# CADDX_v1.net
KiCad netlist of a schematic drawn in Altium Designer
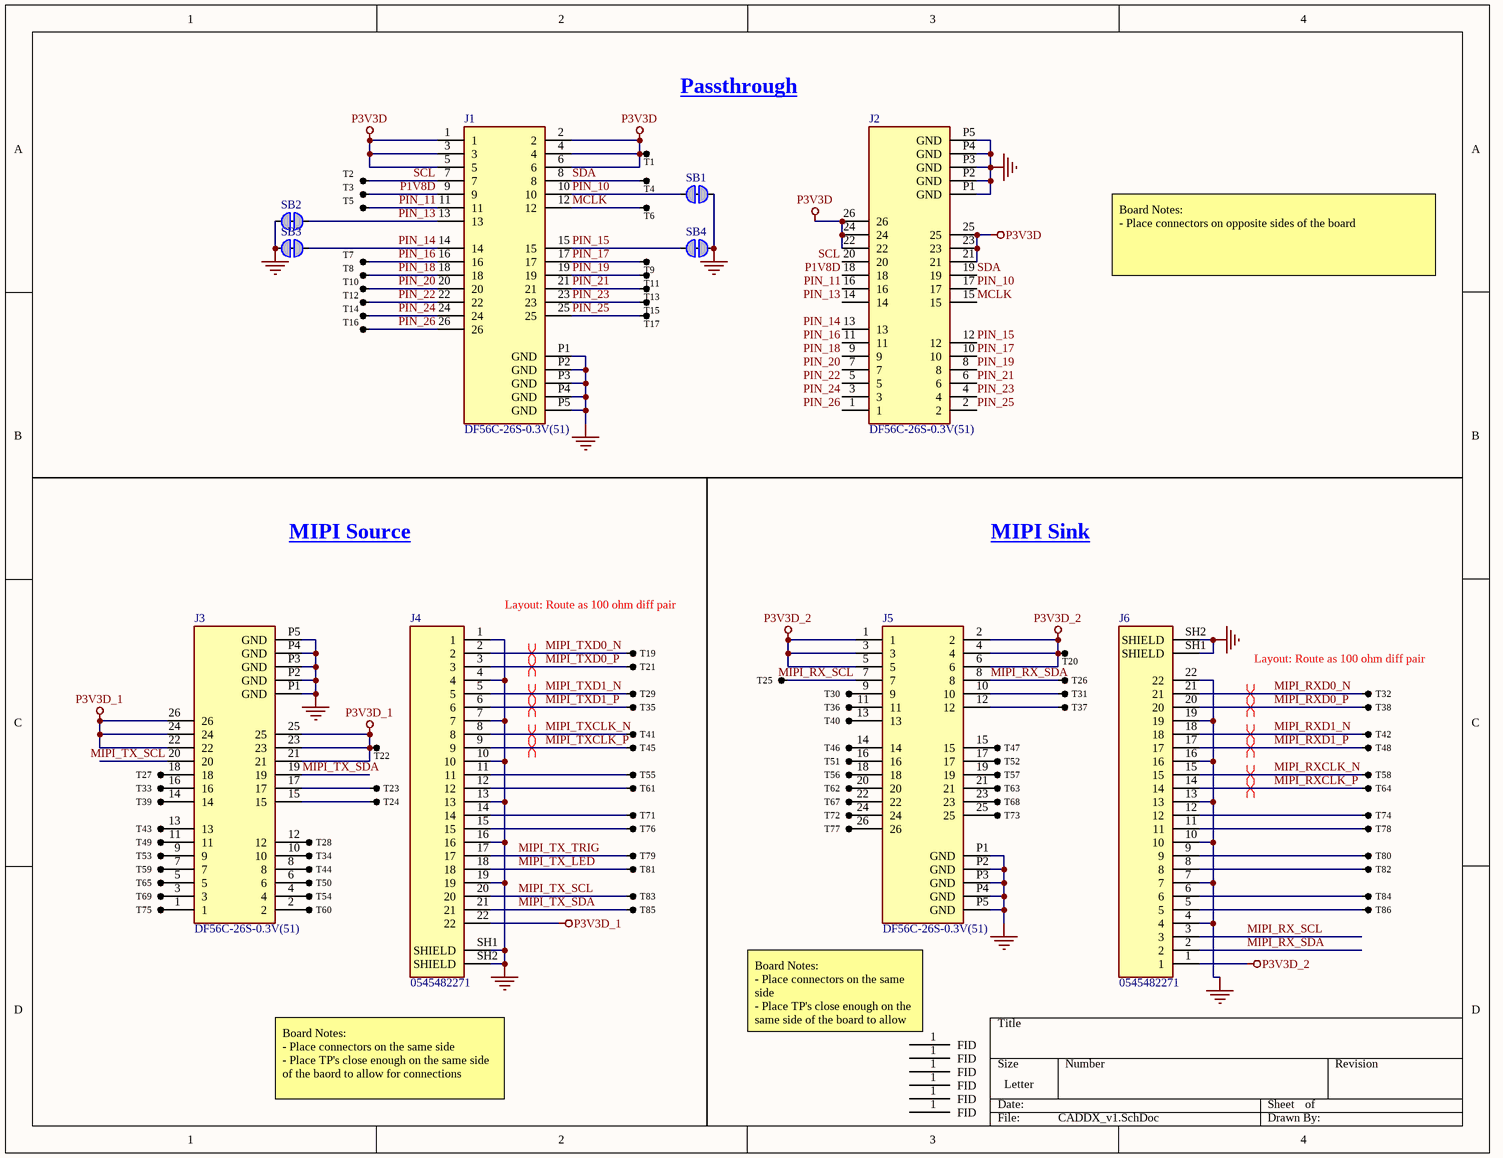
[diagram p0: CADDX_v1.SchDoc]

(export (version "E")
  (design (tool "Eeschema 10.0.6"))
  (components
    (comp (ref "FID1") (value "FID") (footprint "FID_040") (libsource (lib "AiC RVP Adapter") (part "FID")))
    (comp (ref "FID2") (value "FID") (footprint "FID_040") (libsource (lib "AiC RVP Adapter") (part "FID")))
    (comp (ref "FID3") (value "FID") (footprint "FID_040") (libsource (lib "AiC RVP Adapter") (part "FID")))
    (comp (ref "FID4") (value "FID") (footprint "FID_040") (libsource (lib "AiC RVP Adapter") (part "FID")))
    (comp (ref "FID5") (value "FID") (footprint "FID_040") (libsource (lib "AiC RVP Adapter") (part "FID")))
    (comp (ref "FID6") (value "FID") (footprint "FID_040") (libsource (lib "AiC RVP Adapter") (part "FID")))
    (comp (ref "J1")
      (value "DF56C-26S-0.3V(51)")
      (footprint "HRS_DF56C-26S-0.3V(51)")
      (description "0.3mm Pitch, Vertical Mating, Board-to-Fine Coaxial Cable, -35 ℃ to 85 ℃, RoHS")
      (fields (field (name "MANUFACTURER") "Hirose"))
      (libsource (lib "CADDX_passthrough") (part "DF56C-26S-0.3V(51)"))
    )
    (comp (ref "J2")
      (value "DF56C-26S-0.3V(51)")
      (footprint "HRS_DF56C-26S-0.3V(51)")
      (description "0.3mm Pitch, Vertical Mating, Board-to-Fine Coaxial Cable, -35 ℃ to 85 ℃, RoHS")
      (fields (field (name "MANUFACTURER") "Hirose"))
      (libsource (lib "") (part "DF56C-26S-0.3V(51)_1"))
    )
    (comp (ref "J3")
      (value "DF56C-26S-0.3V(51)")
      (footprint "HRS_DF56C-26S-0.3V(51)")
      (description "0.3mm Pitch, Vertical Mating, Board-to-Fine Coaxial Cable, -35 ℃ to 85 ℃, RoHS")
      (fields (field (name "MANUFACTURER") "Hirose"))
      (libsource (lib "") (part "DF56C-26S-0.3V(51)_1"))
    )
    (comp (ref "J4")
      (value "0545482271")
      (footprint "MOLEX_54548-2271")
      (description "CONN FFC BOTTOM 22POS 0.50MM R/A")
      (fields (field (name "MANUFACTURER") "Molex"))
      (libsource (lib "CADDX_passthrough") (part "54548-2271"))
    )
    (comp (ref "J5")
      (value "DF56C-26S-0.3V(51)")
      (footprint "HRS_DF56C-26S-0.3V(51)")
      (description "0.3mm Pitch, Vertical Mating, Board-to-Fine Coaxial Cable, -35 ℃ to 85 ℃, RoHS")
      (fields (field (name "MANUFACTURER") "Hirose"))
      (libsource (lib "CADDX_passthrough") (part "DF56C-26S-0.3V(51)"))
    )
    (comp (ref "J6")
      (value "0545482271")
      (footprint "MOLEX_54548-2271")
      (description "CONN FFC BOTTOM 22POS 0.50MM R/A")
      (fields (field (name "MANUFACTURER") "Molex"))
      (libsource (lib "") (part "54548-2271_1"))
    )
    (comp (ref "SB1")
      (value "Solderbridge")
      (footprint "Solderbridge_Shorted")
      (description "Shorted Solderbridge")
      (fields
        (field (name "PART NUMBER") "Solderbridge Shorted")
        (field (name "PUBLISHER") "Nordic Semiconductor")
      )
      (libsource (lib "Tiger_Ti180") (part "Solderbridge Shorted"))
    )
    (comp (ref "SB2")
      (value "Solderbridge")
      (footprint "Solderbridge_Shorted")
      (description "Shorted Solderbridge")
      (fields
        (field (name "PART NUMBER") "Solderbridge Shorted")
        (field (name "PUBLISHER") "Nordic Semiconductor")
      )
      (libsource (lib "Tiger_Ti180") (part "Solderbridge Shorted"))
    )
    (comp (ref "SB3")
      (value "Solderbridge")
      (footprint "Solderbridge_Shorted")
      (description "Shorted Solderbridge")
      (fields
        (field (name "PART NUMBER") "Solderbridge Shorted")
        (field (name "PUBLISHER") "Nordic Semiconductor")
      )
      (libsource (lib "Tiger_Ti180") (part "Solderbridge Shorted"))
    )
    (comp (ref "SB4")
      (value "Solderbridge")
      (footprint "Solderbridge_Shorted")
      (description "Shorted Solderbridge")
      (fields
        (field (name "PART NUMBER") "Solderbridge Shorted")
        (field (name "PUBLISHER") "Nordic Semiconductor")
      )
      (libsource (lib "Tiger_Ti180") (part "Solderbridge Shorted"))
    )
    (comp (ref "T1")
      (value "~")
      (footprint "TP 1mm")
      (description "test point")
      (libsource (lib "Tiger_Ti180") (part "TP_S"))
    )
    (comp (ref "T2")
      (value "~")
      (footprint "TP 1mm")
      (description "test point")
      (libsource (lib "Tiger_Ti180") (part "TP_S"))
    )
    (comp (ref "T3")
      (value "~")
      (footprint "TP 1mm")
      (description "test point")
      (libsource (lib "Tiger_Ti180") (part "TP_S"))
    )
    (comp (ref "T4")
      (value "~")
      (footprint "TP 1mm")
      (description "test point")
      (libsource (lib "Tiger_Ti180") (part "TP_S"))
    )
    (comp (ref "T5")
      (value "~")
      (footprint "TP 1mm")
      (description "test point")
      (libsource (lib "Tiger_Ti180") (part "TP_S"))
    )
    (comp (ref "T6")
      (value "~")
      (footprint "TP 1mm")
      (description "test point")
      (libsource (lib "Tiger_Ti180") (part "TP_S"))
    )
    (comp (ref "T7")
      (value "~")
      (footprint "TP 1mm")
      (description "test point")
      (libsource (lib "Tiger_Ti180") (part "TP_S"))
    )
    (comp (ref "T8")
      (value "~")
      (footprint "TP 1mm")
      (description "test point")
      (libsource (lib "Tiger_Ti180") (part "TP_S"))
    )
    (comp (ref "T9")
      (value "~")
      (footprint "TP 1mm")
      (description "test point")
      (libsource (lib "Tiger_Ti180") (part "TP_S"))
    )
    (comp (ref "T10")
      (value "~")
      (footprint "TP 1mm")
      (description "test point")
      (libsource (lib "Tiger_Ti180") (part "TP_S"))
    )
    (comp (ref "T11")
      (value "~")
      (footprint "TP 1mm")
      (description "test point")
      (libsource (lib "Tiger_Ti180") (part "TP_S"))
    )
    (comp (ref "T12")
      (value "~")
      (footprint "TP 1mm")
      (description "test point")
      (libsource (lib "Tiger_Ti180") (part "TP_S"))
    )
    (comp (ref "T13")
      (value "~")
      (footprint "TP 1mm")
      (description "test point")
      (libsource (lib "Tiger_Ti180") (part "TP_S"))
    )
    (comp (ref "T14")
      (value "~")
      (footprint "TP 1mm")
      (description "test point")
      (libsource (lib "Tiger_Ti180") (part "TP_S"))
    )
    (comp (ref "T15")
      (value "~")
      (footprint "TP 1mm")
      (description "test point")
      (libsource (lib "Tiger_Ti180") (part "TP_S"))
    )
    (comp (ref "T16")
      (value "~")
      (footprint "TP 1mm")
      (description "test point")
      (libsource (lib "Tiger_Ti180") (part "TP_S"))
    )
    (comp (ref "T17")
      (value "~")
      (footprint "TP 1mm")
      (description "test point")
      (libsource (lib "Tiger_Ti180") (part "TP_S"))
    )
    (comp (ref "T19")
      (value "~")
      (footprint "TP 1mm")
      (description "test point")
      (libsource (lib "Tiger_Ti180") (part "TP_S"))
    )
    (comp (ref "T20")
      (value "~")
      (footprint "TP 1mm")
      (description "test point")
      (libsource (lib "Tiger_Ti180") (part "TP_S"))
    )
    (comp (ref "T21")
      (value "~")
      (footprint "TP 1mm")
      (description "test point")
      (libsource (lib "Tiger_Ti180") (part "TP_S"))
    )
    (comp (ref "T22")
      (value "~")
      (footprint "TP 1mm")
      (description "test point")
      (libsource (lib "Tiger_Ti180") (part "TP_S"))
    )
    (comp (ref "T23")
      (value "~")
      (footprint "TP 1mm")
      (description "test point")
      (libsource (lib "Tiger_Ti180") (part "TP_S"))
    )
    (comp (ref "T24")
      (value "~")
      (footprint "TP 1mm")
      (description "test point")
      (libsource (lib "Tiger_Ti180") (part "TP_S"))
    )
    (comp (ref "T25")
      (value "~")
      (footprint "TP 1mm")
      (description "test point")
      (libsource (lib "Tiger_Ti180") (part "TP_S"))
    )
    (comp (ref "T26")
      (value "~")
      (footprint "TP 1mm")
      (description "test point")
      (libsource (lib "Tiger_Ti180") (part "TP_S"))
    )
    (comp (ref "T27")
      (value "~")
      (footprint "TP 1mm")
      (description "test point")
      (libsource (lib "Tiger_Ti180") (part "TP_S"))
    )
    (comp (ref "T28")
      (value "~")
      (footprint "TP 1mm")
      (description "test point")
      (libsource (lib "Tiger_Ti180") (part "TP_S"))
    )
    (comp (ref "T29")
      (value "~")
      (footprint "TP 1mm")
      (description "test point")
      (libsource (lib "Tiger_Ti180") (part "TP_S"))
    )
    (comp (ref "T30")
      (value "~")
      (footprint "TP 1mm")
      (description "test point")
      (libsource (lib "Tiger_Ti180") (part "TP_S"))
    )
    (comp (ref "T31")
      (value "~")
      (footprint "TP 1mm")
      (description "test point")
      (libsource (lib "Tiger_Ti180") (part "TP_S"))
    )
    (comp (ref "T32")
      (value "~")
      (footprint "TP 1mm")
      (description "test point")
      (libsource (lib "Tiger_Ti180") (part "TP_S"))
    )
    (comp (ref "T33")
      (value "~")
      (footprint "TP 1mm")
      (description "test point")
      (libsource (lib "Tiger_Ti180") (part "TP_S"))
    )
    (comp (ref "T34")
      (value "~")
      (footprint "TP 1mm")
      (description "test point")
      (libsource (lib "Tiger_Ti180") (part "TP_S"))
    )
    (comp (ref "T35")
      (value "~")
      (footprint "TP 1mm")
      (description "test point")
      (libsource (lib "Tiger_Ti180") (part "TP_S"))
    )
    (comp (ref "T36")
      (value "~")
      (footprint "TP 1mm")
      (description "test point")
      (libsource (lib "Tiger_Ti180") (part "TP_S"))
    )
    (comp (ref "T37")
      (value "~")
      (footprint "TP 1mm")
      (description "test point")
      (libsource (lib "Tiger_Ti180") (part "TP_S"))
    )
    (comp (ref "T38")
      (value "~")
      (footprint "TP 1mm")
      (description "test point")
      (libsource (lib "Tiger_Ti180") (part "TP_S"))
    )
    (comp (ref "T39")
      (value "~")
      (footprint "TP 1mm")
      (description "test point")
      (libsource (lib "Tiger_Ti180") (part "TP_S"))
    )
    (comp (ref "T40")
      (value "~")
      (footprint "TP 1mm")
      (description "test point")
      (libsource (lib "Tiger_Ti180") (part "TP_S"))
    )
    (comp (ref "T41")
      (value "~")
      (footprint "TP 1mm")
      (description "test point")
      (libsource (lib "Tiger_Ti180") (part "TP_S"))
    )
    (comp (ref "T42")
      (value "~")
      (footprint "TP 1mm")
      (description "test point")
      (libsource (lib "Tiger_Ti180") (part "TP_S"))
    )
    (comp (ref "T43")
      (value "~")
      (footprint "TP 1mm")
      (description "test point")
      (libsource (lib "Tiger_Ti180") (part "TP_S"))
    )
    (comp (ref "T44")
      (value "~")
      (footprint "TP 1mm")
      (description "test point")
      (libsource (lib "Tiger_Ti180") (part "TP_S"))
    )
    (comp (ref "T45")
      (value "~")
      (footprint "TP 1mm")
      (description "test point")
      (libsource (lib "Tiger_Ti180") (part "TP_S"))
    )
    (comp (ref "T46")
      (value "~")
      (footprint "TP 1mm")
      (description "test point")
      (libsource (lib "Tiger_Ti180") (part "TP_S"))
    )
    (comp (ref "T47")
      (value "~")
      (footprint "TP 1mm")
      (description "test point")
      (libsource (lib "Tiger_Ti180") (part "TP_S"))
    )
    (comp (ref "T48")
      (value "~")
      (footprint "TP 1mm")
      (description "test point")
      (libsource (lib "Tiger_Ti180") (part "TP_S"))
    )
    (comp (ref "T49")
      (value "~")
      (footprint "TP 1mm")
      (description "test point")
      (libsource (lib "Tiger_Ti180") (part "TP_S"))
    )
    (comp (ref "T50")
      (value "~")
      (footprint "TP 1mm")
      (description "test point")
      (libsource (lib "Tiger_Ti180") (part "TP_S"))
    )
    (comp (ref "T51")
      (value "~")
      (footprint "TP 1mm")
      (description "test point")
      (libsource (lib "Tiger_Ti180") (part "TP_S"))
    )
    (comp (ref "T52")
      (value "~")
      (footprint "TP 1mm")
      (description "test point")
      (libsource (lib "Tiger_Ti180") (part "TP_S"))
    )
    (comp (ref "T53")
      (value "~")
      (footprint "TP 1mm")
      (description "test point")
      (libsource (lib "Tiger_Ti180") (part "TP_S"))
    )
    (comp (ref "T54")
      (value "~")
      (footprint "TP 1mm")
      (description "test point")
      (libsource (lib "Tiger_Ti180") (part "TP_S"))
    )
    (comp (ref "T55")
      (value "~")
      (footprint "TP 1mm")
      (description "test point")
      (libsource (lib "Tiger_Ti180") (part "TP_S"))
    )
    (comp (ref "T56")
      (value "~")
      (footprint "TP 1mm")
      (description "test point")
      (libsource (lib "Tiger_Ti180") (part "TP_S"))
    )
    (comp (ref "T57")
      (value "~")
      (footprint "TP 1mm")
      (description "test point")
      (libsource (lib "Tiger_Ti180") (part "TP_S"))
    )
    (comp (ref "T58")
      (value "~")
      (footprint "TP 1mm")
      (description "test point")
      (libsource (lib "Tiger_Ti180") (part "TP_S"))
    )
    (comp (ref "T59")
      (value "~")
      (footprint "TP 1mm")
      (description "test point")
      (libsource (lib "Tiger_Ti180") (part "TP_S"))
    )
    (comp (ref "T60")
      (value "~")
      (footprint "TP 1mm")
      (description "test point")
      (libsource (lib "Tiger_Ti180") (part "TP_S"))
    )
    (comp (ref "T61")
      (value "~")
      (footprint "TP 1mm")
      (description "test point")
      (libsource (lib "Tiger_Ti180") (part "TP_S"))
    )
    (comp (ref "T62")
      (value "~")
      (footprint "TP 1mm")
      (description "test point")
      (libsource (lib "Tiger_Ti180") (part "TP_S"))
    )
    (comp (ref "T63")
      (value "~")
      (footprint "TP 1mm")
      (description "test point")
      (libsource (lib "Tiger_Ti180") (part "TP_S"))
    )
    (comp (ref "T64")
      (value "~")
      (footprint "TP 1mm")
      (description "test point")
      (libsource (lib "Tiger_Ti180") (part "TP_S"))
    )
    (comp (ref "T65")
      (value "~")
      (footprint "TP 1mm")
      (description "test point")
      (libsource (lib "Tiger_Ti180") (part "TP_S"))
    )
    (comp (ref "T67")
      (value "~")
      (footprint "TP 1mm")
      (description "test point")
      (libsource (lib "Tiger_Ti180") (part "TP_S"))
    )
    (comp (ref "T68")
      (value "~")
      (footprint "TP 1mm")
      (description "test point")
      (libsource (lib "Tiger_Ti180") (part "TP_S"))
    )
    (comp (ref "T69")
      (value "~")
      (footprint "TP 1mm")
      (description "test point")
      (libsource (lib "Tiger_Ti180") (part "TP_S"))
    )
    (comp (ref "T71")
      (value "~")
      (footprint "TP 1mm")
      (description "test point")
      (libsource (lib "Tiger_Ti180") (part "TP_S"))
    )
    (comp (ref "T72")
      (value "~")
      (footprint "TP 1mm")
      (description "test point")
      (libsource (lib "Tiger_Ti180") (part "TP_S"))
    )
    (comp (ref "T73")
      (value "~")
      (footprint "TP 1mm")
      (description "test point")
      (libsource (lib "Tiger_Ti180") (part "TP_S"))
    )
    (comp (ref "T74")
      (value "~")
      (footprint "TP 1mm")
      (description "test point")
      (libsource (lib "Tiger_Ti180") (part "TP_S"))
    )
    (comp (ref "T75")
      (value "~")
      (footprint "TP 1mm")
      (description "test point")
      (libsource (lib "Tiger_Ti180") (part "TP_S"))
    )
    (comp (ref "T76")
      (value "~")
      (footprint "TP 1mm")
      (description "test point")
      (libsource (lib "Tiger_Ti180") (part "TP_S"))
    )
    (comp (ref "T77")
      (value "~")
      (footprint "TP 1mm")
      (description "test point")
      (libsource (lib "Tiger_Ti180") (part "TP_S"))
    )
    (comp (ref "T78")
      (value "~")
      (footprint "TP 1mm")
      (description "test point")
      (libsource (lib "Tiger_Ti180") (part "TP_S"))
    )
    (comp (ref "T79")
      (value "~")
      (footprint "TP 1mm")
      (description "test point")
      (libsource (lib "Tiger_Ti180") (part "TP_S"))
    )
    (comp (ref "T80")
      (value "~")
      (footprint "TP 1mm")
      (description "test point")
      (libsource (lib "Tiger_Ti180") (part "TP_S"))
    )
    (comp (ref "T81")
      (value "~")
      (footprint "TP 1mm")
      (description "test point")
      (libsource (lib "Tiger_Ti180") (part "TP_S"))
    )
    (comp (ref "T82")
      (value "~")
      (footprint "TP 1mm")
      (description "test point")
      (libsource (lib "Tiger_Ti180") (part "TP_S"))
    )
    (comp (ref "T83")
      (value "~")
      (footprint "TP 1mm")
      (description "test point")
      (libsource (lib "Tiger_Ti180") (part "TP_S"))
    )
    (comp (ref "T84")
      (value "~")
      (footprint "TP 1mm")
      (description "test point")
      (libsource (lib "Tiger_Ti180") (part "TP_S"))
    )
    (comp (ref "T85")
      (value "~")
      (footprint "TP 1mm")
      (description "test point")
      (libsource (lib "Tiger_Ti180") (part "TP_S"))
    )
    (comp (ref "T86")
      (value "~")
      (footprint "TP 1mm")
      (description "test point")
      (libsource (lib "Tiger_Ti180") (part "TP_S"))
    )
  )
  (nets
    (net (code "1") (name "/MCLK") (class "Default")
      (node (ref "J1") (pin "12") (pinfunction "12_12") (pintype "passive"))
      (node (ref "J2") (pin "15") (pinfunction "15_15") (pintype "passive"))
      (node (ref "T6") (pin "1") (pintype "passive"))
    )
    (net (code "2") (name "/MIPI_RXCLK_N") (class "Default")
      (node (ref "J6") (pin "15") (pinfunction "15_15") (pintype "passive"))
      (node (ref "T58") (pin "1") (pintype "passive"))
    )
    (net (code "3") (name "/MIPI_RXCLK_P") (class "Default")
      (node (ref "J6") (pin "14") (pinfunction "14_14") (pintype "passive"))
      (node (ref "T64") (pin "1") (pintype "passive"))
    )
    (net (code "4") (name "/MIPI_RXD0_N") (class "Default")
      (node (ref "J6") (pin "21") (pinfunction "21_21") (pintype "passive"))
      (node (ref "T32") (pin "1") (pintype "passive"))
    )
    (net (code "5") (name "/MIPI_RXD0_P") (class "Default")
      (node (ref "J6") (pin "20") (pinfunction "20_20") (pintype "passive"))
      (node (ref "T38") (pin "1") (pintype "passive"))
    )
    (net (code "6") (name "/MIPI_RXD1_N") (class "Default")
      (node (ref "J6") (pin "18") (pinfunction "18_18") (pintype "passive"))
      (node (ref "T42") (pin "1") (pintype "passive"))
    )
    (net (code "7") (name "/MIPI_RXD1_P") (class "Default")
      (node (ref "J6") (pin "17") (pinfunction "17_17") (pintype "passive"))
      (node (ref "T48") (pin "1") (pintype "passive"))
    )
    (net (code "8") (name "/MIPI_RX_SCL") (class "Default")
      (node (ref "J5") (pin "7") (pinfunction "7_7") (pintype "passive"))
      (node (ref "J6") (pin "3") (pinfunction "3_3") (pintype "passive"))
      (node (ref "T25") (pin "1") (pintype "passive"))
    )
    (net (code "9") (name "/MIPI_RX_SDA") (class "Default")
      (node (ref "J5") (pin "8") (pinfunction "8_8") (pintype "passive"))
      (node (ref "J6") (pin "2") (pinfunction "2_2") (pintype "passive"))
      (node (ref "T26") (pin "1") (pintype "passive"))
    )
    (net (code "10") (name "/MIPI_TXCLK_N") (class "Default")
      (node (ref "J4") (pin "8") (pinfunction "8_8") (pintype "passive"))
      (node (ref "T41") (pin "1") (pintype "passive"))
    )
    (net (code "11") (name "/MIPI_TXCLK_P") (class "Default")
      (node (ref "J4") (pin "9") (pinfunction "9_9") (pintype "passive"))
      (node (ref "T45") (pin "1") (pintype "passive"))
    )
    (net (code "12") (name "/MIPI_TXD0_N") (class "Default")
      (node (ref "J4") (pin "2") (pinfunction "2_2") (pintype "passive"))
      (node (ref "T19") (pin "1") (pintype "passive"))
    )
    (net (code "13") (name "/MIPI_TXD0_P") (class "Default")
      (node (ref "J4") (pin "3") (pinfunction "3_3") (pintype "passive"))
      (node (ref "T21") (pin "1") (pintype "passive"))
    )
    (net (code "14") (name "/MIPI_TXD1_N") (class "Default")
      (node (ref "J4") (pin "5") (pinfunction "5_5") (pintype "passive"))
      (node (ref "T29") (pin "1") (pintype "passive"))
    )
    (net (code "15") (name "/MIPI_TXD1_P") (class "Default")
      (node (ref "J4") (pin "6") (pinfunction "6_6") (pintype "passive"))
      (node (ref "T35") (pin "1") (pintype "passive"))
    )
    (net (code "16") (name "/MIPI_TX_LED") (class "Default")
      (node (ref "J4") (pin "18") (pinfunction "18_18") (pintype "passive"))
      (node (ref "T81") (pin "1") (pintype "passive"))
    )
    (net (code "17") (name "/MIPI_TX_SCL") (class "Default")
      (node (ref "J3") (pin "20") (pinfunction "20_20") (pintype "passive"))
      (node (ref "J4") (pin "20") (pinfunction "20_20") (pintype "passive"))
      (node (ref "T83") (pin "1") (pintype "passive"))
    )
    (net (code "18") (name "/MIPI_TX_SDA") (class "Default")
      (node (ref "J3") (pin "19") (pinfunction "19_19") (pintype "passive"))
      (node (ref "J4") (pin "21") (pinfunction "21_21") (pintype "passive"))
      (node (ref "T85") (pin "1") (pintype "passive"))
    )
    (net (code "19") (name "/MIPI_TX_TRIG") (class "Default")
      (node (ref "J4") (pin "17") (pinfunction "17_17") (pintype "passive"))
      (node (ref "T79") (pin "1") (pintype "passive"))
    )
    (net (code "20") (name "/P1V8D") (class "Default")
      (node (ref "J1") (pin "9") (pinfunction "9_9") (pintype "passive"))
      (node (ref "J2") (pin "18") (pinfunction "18_18") (pintype "passive"))
      (node (ref "T3") (pin "1") (pintype "passive"))
    )
    (net (code "21") (name "/PIN_10") (class "Default")
      (node (ref "J1") (pin "10") (pinfunction "10_10") (pintype "passive"))
      (node (ref "J2") (pin "17") (pinfunction "17_17") (pintype "passive"))
      (node (ref "SB1") (pin "2") (pinfunction "1_2") (pintype "passive"))
    )
    (net (code "22") (name "/PIN_11") (class "Default")
      (node (ref "J1") (pin "11") (pinfunction "11_11") (pintype "passive"))
      (node (ref "J2") (pin "16") (pinfunction "16_16") (pintype "passive"))
      (node (ref "T5") (pin "1") (pintype "passive"))
    )
    (net (code "23") (name "/PIN_13") (class "Default")
      (node (ref "J1") (pin "13") (pinfunction "13_13") (pintype "passive"))
      (node (ref "J2") (pin "14") (pinfunction "14_14") (pintype "passive"))
      (node (ref "SB2") (pin "1") (pinfunction "0_1") (pintype "passive"))
    )
    (net (code "24") (name "/PIN_14") (class "Default")
      (node (ref "J1") (pin "14") (pinfunction "14_14") (pintype "passive"))
      (node (ref "J2") (pin "13") (pinfunction "13_13") (pintype "passive"))
      (node (ref "SB3") (pin "1") (pinfunction "0_1") (pintype "passive"))
    )
    (net (code "25") (name "/PIN_15") (class "Default")
      (node (ref "J1") (pin "15") (pinfunction "15_15") (pintype "passive"))
      (node (ref "J2") (pin "12") (pinfunction "12_12") (pintype "passive"))
      (node (ref "SB4") (pin "2") (pinfunction "1_2") (pintype "passive"))
    )
    (net (code "26") (name "/PIN_16") (class "Default")
      (node (ref "J1") (pin "16") (pinfunction "16_16") (pintype "passive"))
      (node (ref "J2") (pin "11") (pinfunction "11_11") (pintype "passive"))
      (node (ref "T7") (pin "1") (pintype "passive"))
    )
    (net (code "27") (name "/PIN_17") (class "Default")
      (node (ref "J1") (pin "17") (pinfunction "17_17") (pintype "passive"))
      (node (ref "J2") (pin "10") (pinfunction "10_10") (pintype "passive"))
      (node (ref "T9") (pin "1") (pintype "passive"))
    )
    (net (code "28") (name "/PIN_18") (class "Default")
      (node (ref "J1") (pin "18") (pinfunction "18_18") (pintype "passive"))
      (node (ref "J2") (pin "9") (pinfunction "9_9") (pintype "passive"))
      (node (ref "T8") (pin "1") (pintype "passive"))
    )
    (net (code "29") (name "/PIN_19") (class "Default")
      (node (ref "J1") (pin "19") (pinfunction "19_19") (pintype "passive"))
      (node (ref "J2") (pin "8") (pinfunction "8_8") (pintype "passive"))
      (node (ref "T11") (pin "1") (pintype "passive"))
    )
    (net (code "30") (name "/PIN_20") (class "Default")
      (node (ref "J1") (pin "20") (pinfunction "20_20") (pintype "passive"))
      (node (ref "J2") (pin "7") (pinfunction "7_7") (pintype "passive"))
      (node (ref "T10") (pin "1") (pintype "passive"))
    )
    (net (code "31") (name "/PIN_21") (class "Default")
      (node (ref "J1") (pin "21") (pinfunction "21_21") (pintype "passive"))
      (node (ref "J2") (pin "6") (pinfunction "6_6") (pintype "passive"))
      (node (ref "T13") (pin "1") (pintype "passive"))
    )
    (net (code "32") (name "/PIN_22") (class "Default")
      (node (ref "J1") (pin "22") (pinfunction "22_22") (pintype "passive"))
      (node (ref "J2") (pin "5") (pinfunction "5_5") (pintype "passive"))
      (node (ref "T12") (pin "1") (pintype "passive"))
    )
    (net (code "33") (name "/PIN_23") (class "Default")
      (node (ref "J1") (pin "23") (pinfunction "23_23") (pintype "passive"))
      (node (ref "J2") (pin "4") (pinfunction "4_4") (pintype "passive"))
      (node (ref "T15") (pin "1") (pintype "passive"))
    )
    (net (code "34") (name "/PIN_24") (class "Default")
      (node (ref "J1") (pin "24") (pinfunction "24_24") (pintype "passive"))
      (node (ref "J2") (pin "3") (pinfunction "3_3") (pintype "passive"))
      (node (ref "T14") (pin "1") (pintype "passive"))
    )
    (net (code "35") (name "/PIN_25") (class "Default")
      (node (ref "J1") (pin "25") (pinfunction "25_25") (pintype "passive"))
      (node (ref "J2") (pin "2") (pinfunction "2_2") (pintype "passive"))
      (node (ref "T17") (pin "1") (pintype "passive"))
    )
    (net (code "36") (name "/PIN_26") (class "Default")
      (node (ref "J1") (pin "26") (pinfunction "26_26") (pintype "passive"))
      (node (ref "J2") (pin "1") (pinfunction "1_1") (pintype "passive"))
      (node (ref "T16") (pin "1") (pintype "passive"))
    )
    (net (code "37") (name "/SCL") (class "Default")
      (node (ref "J1") (pin "7") (pinfunction "7_7") (pintype "passive"))
      (node (ref "J2") (pin "20") (pinfunction "20_20") (pintype "passive"))
      (node (ref "T2") (pin "1") (pintype "passive"))
    )
    (net (code "38") (name "/SDA") (class "Default")
      (node (ref "J1") (pin "8") (pinfunction "8_8") (pintype "passive"))
      (node (ref "J2") (pin "19") (pinfunction "19_19") (pintype "passive"))
      (node (ref "T4") (pin "1") (pintype "passive"))
    )
    (net (code "39") (name "GND") (class "Default")
      (node (ref "J1") (pin "P1") (pinfunction "GND_P1") (pintype "power_in"))
      (node (ref "J1") (pin "P2") (pinfunction "GND_P2") (pintype "power_in"))
      (node (ref "J1") (pin "P3") (pinfunction "GND_P3") (pintype "power_in"))
      (node (ref "J1") (pin "P4") (pinfunction "GND_P4") (pintype "power_in"))
      (node (ref "J1") (pin "P5") (pinfunction "GND_P5") (pintype "power_in"))
      (node (ref "J2") (pin "P1") (pinfunction "GND_P1") (pintype "power_in"))
      (node (ref "J2") (pin "P2") (pinfunction "GND_P2") (pintype "power_in"))
      (node (ref "J2") (pin "P3") (pinfunction "GND_P3") (pintype "power_in"))
      (node (ref "J2") (pin "P4") (pinfunction "GND_P4") (pintype "power_in"))
      (node (ref "J2") (pin "P5") (pinfunction "GND_P5") (pintype "power_in"))
      (node (ref "J3") (pin "P1") (pinfunction "GND_P1") (pintype "power_in"))
      (node (ref "J3") (pin "P2") (pinfunction "GND_P2") (pintype "power_in"))
      (node (ref "J3") (pin "P3") (pinfunction "GND_P3") (pintype "power_in"))
      (node (ref "J3") (pin "P4") (pinfunction "GND_P4") (pintype "power_in"))
      (node (ref "J3") (pin "P5") (pinfunction "GND_P5") (pintype "power_in"))
      (node (ref "J4") (pin "1") (pinfunction "1_1") (pintype "passive"))
      (node (ref "J4") (pin "10") (pinfunction "10_10") (pintype "passive"))
      (node (ref "J4") (pin "13") (pinfunction "13_13") (pintype "passive"))
      (node (ref "J4") (pin "16") (pinfunction "16_16") (pintype "passive"))
      (node (ref "J4") (pin "19") (pinfunction "19_19") (pintype "passive"))
      (node (ref "J4") (pin "4") (pinfunction "4_4") (pintype "passive"))
      (node (ref "J4") (pin "7") (pinfunction "7_7") (pintype "passive"))
      (node (ref "J4") (pin "SH1") (pinfunction "SHIELD_SH1") (pintype "passive"))
      (node (ref "J4") (pin "SH2") (pinfunction "SHIELD_SH2") (pintype "passive"))
      (node (ref "J5") (pin "P1") (pinfunction "GND_P1") (pintype "power_in"))
      (node (ref "J5") (pin "P2") (pinfunction "GND_P2") (pintype "power_in"))
      (node (ref "J5") (pin "P3") (pinfunction "GND_P3") (pintype "power_in"))
      (node (ref "J5") (pin "P4") (pinfunction "GND_P4") (pintype "power_in"))
      (node (ref "J5") (pin "P5") (pinfunction "GND_P5") (pintype "power_in"))
      (node (ref "J6") (pin "10") (pinfunction "10_10") (pintype "passive"))
      (node (ref "J6") (pin "13") (pinfunction "13_13") (pintype "passive"))
      (node (ref "J6") (pin "16") (pinfunction "16_16") (pintype "passive"))
      (node (ref "J6") (pin "19") (pinfunction "19_19") (pintype "passive"))
      (node (ref "J6") (pin "22") (pinfunction "22_22") (pintype "passive"))
      (node (ref "J6") (pin "4") (pinfunction "4_4") (pintype "passive"))
      (node (ref "J6") (pin "7") (pinfunction "7_7") (pintype "passive"))
      (node (ref "J6") (pin "SH1") (pinfunction "SHIELD_SH1") (pintype "passive"))
      (node (ref "J6") (pin "SH2") (pinfunction "SHIELD_SH2") (pintype "passive"))
      (node (ref "SB1") (pin "1") (pinfunction "0_1") (pintype "passive"))
      (node (ref "SB2") (pin "2") (pinfunction "1_2") (pintype "passive"))
      (node (ref "SB3") (pin "2") (pinfunction "1_2") (pintype "passive"))
      (node (ref "SB4") (pin "1") (pinfunction "0_1") (pintype "passive"))
    )
    (net (code "40") (name "Net-(J3-Pad1)") (class "Default")
      (node (ref "J3") (pin "1") (pinfunction "1_1") (pintype "passive"))
      (node (ref "T75") (pin "1") (pintype "passive"))
    )
    (net (code "41") (name "Net-(J3-Pad2)") (class "Default")
      (node (ref "J3") (pin "2") (pinfunction "2_2") (pintype "passive"))
      (node (ref "T60") (pin "1") (pintype "passive"))
    )
    (net (code "42") (name "Net-(J3-Pad3)") (class "Default")
      (node (ref "J3") (pin "3") (pinfunction "3_3") (pintype "passive"))
      (node (ref "T69") (pin "1") (pintype "passive"))
    )
    (net (code "43") (name "Net-(J3-Pad4)") (class "Default")
      (node (ref "J3") (pin "4") (pinfunction "4_4") (pintype "passive"))
      (node (ref "T54") (pin "1") (pintype "passive"))
    )
    (net (code "44") (name "Net-(J3-Pad5)") (class "Default")
      (node (ref "J3") (pin "5") (pinfunction "5_5") (pintype "passive"))
      (node (ref "T65") (pin "1") (pintype "passive"))
    )
    (net (code "45") (name "Net-(J3-Pad6)") (class "Default")
      (node (ref "J3") (pin "6") (pinfunction "6_6") (pintype "passive"))
      (node (ref "T50") (pin "1") (pintype "passive"))
    )
    (net (code "46") (name "Net-(J3-Pad7)") (class "Default")
      (node (ref "J3") (pin "7") (pinfunction "7_7") (pintype "passive"))
      (node (ref "T59") (pin "1") (pintype "passive"))
    )
    (net (code "47") (name "Net-(J3-Pad8)") (class "Default")
      (node (ref "J3") (pin "8") (pinfunction "8_8") (pintype "passive"))
      (node (ref "T44") (pin "1") (pintype "passive"))
    )
    (net (code "48") (name "Net-(J3-Pad9)") (class "Default")
      (node (ref "J3") (pin "9") (pinfunction "9_9") (pintype "passive"))
      (node (ref "T53") (pin "1") (pintype "passive"))
    )
    (net (code "49") (name "Net-(J3-Pad10)") (class "Default")
      (node (ref "J3") (pin "10") (pinfunction "10_10") (pintype "passive"))
      (node (ref "T34") (pin "1") (pintype "passive"))
    )
    (net (code "50") (name "Net-(J3-Pad11)") (class "Default")
      (node (ref "J3") (pin "11") (pinfunction "11_11") (pintype "passive"))
      (node (ref "T49") (pin "1") (pintype "passive"))
    )
    (net (code "51") (name "Net-(J3-Pad12)") (class "Default")
      (node (ref "J3") (pin "12") (pinfunction "12_12") (pintype "passive"))
      (node (ref "T28") (pin "1") (pintype "passive"))
    )
    (net (code "52") (name "Net-(J3-Pad13)") (class "Default")
      (node (ref "J3") (pin "13") (pinfunction "13_13") (pintype "passive"))
      (node (ref "T43") (pin "1") (pintype "passive"))
    )
    (net (code "53") (name "Net-(J3-Pad14)") (class "Default")
      (node (ref "J3") (pin "14") (pinfunction "14_14") (pintype "passive"))
      (node (ref "T39") (pin "1") (pintype "passive"))
    )
    (net (code "54") (name "Net-(J3-Pad15)") (class "Default")
      (node (ref "J3") (pin "15") (pinfunction "15_15") (pintype "passive"))
      (node (ref "T24") (pin "1") (pintype "passive"))
    )
    (net (code "55") (name "Net-(J3-Pad16)") (class "Default")
      (node (ref "J3") (pin "16") (pinfunction "16_16") (pintype "passive"))
      (node (ref "T33") (pin "1") (pintype "passive"))
    )
    (net (code "56") (name "Net-(J3-Pad17)") (class "Default")
      (node (ref "J3") (pin "17") (pinfunction "17_17") (pintype "passive"))
      (node (ref "T23") (pin "1") (pintype "passive"))
    )
    (net (code "57") (name "Net-(J3-Pad18)") (class "Default")
      (node (ref "J3") (pin "18") (pinfunction "18_18") (pintype "passive"))
      (node (ref "T27") (pin "1") (pintype "passive"))
    )
    (net (code "58") (name "Net-(J4-Pad11)") (class "Default")
      (node (ref "J4") (pin "11") (pinfunction "11_11") (pintype "passive"))
      (node (ref "T55") (pin "1") (pintype "passive"))
    )
    (net (code "59") (name "Net-(J4-Pad12)") (class "Default")
      (node (ref "J4") (pin "12") (pinfunction "12_12") (pintype "passive"))
      (node (ref "T61") (pin "1") (pintype "passive"))
    )
    (net (code "60") (name "Net-(J4-Pad14)") (class "Default")
      (node (ref "J4") (pin "14") (pinfunction "14_14") (pintype "passive"))
      (node (ref "T71") (pin "1") (pintype "passive"))
    )
    (net (code "61") (name "Net-(J4-Pad15)") (class "Default")
      (node (ref "J4") (pin "15") (pinfunction "15_15") (pintype "passive"))
      (node (ref "T76") (pin "1") (pintype "passive"))
    )
    (net (code "62") (name "Net-(J5-Pad9)") (class "Default")
      (node (ref "J5") (pin "9") (pinfunction "9_9") (pintype "passive"))
      (node (ref "T30") (pin "1") (pintype "passive"))
    )
    (net (code "63") (name "Net-(J5-Pad10)") (class "Default")
      (node (ref "J5") (pin "10") (pinfunction "10_10") (pintype "passive"))
      (node (ref "T31") (pin "1") (pintype "passive"))
    )
    (net (code "64") (name "Net-(J5-Pad11)") (class "Default")
      (node (ref "J5") (pin "11") (pinfunction "11_11") (pintype "passive"))
      (node (ref "T36") (pin "1") (pintype "passive"))
    )
    (net (code "65") (name "Net-(J5-Pad12)") (class "Default")
      (node (ref "J5") (pin "12") (pinfunction "12_12") (pintype "passive"))
      (node (ref "T37") (pin "1") (pintype "passive"))
    )
    (net (code "66") (name "Net-(J5-Pad13)") (class "Default")
      (node (ref "J5") (pin "13") (pinfunction "13_13") (pintype "passive"))
      (node (ref "T40") (pin "1") (pintype "passive"))
    )
    (net (code "67") (name "Net-(J5-Pad14)") (class "Default")
      (node (ref "J5") (pin "14") (pinfunction "14_14") (pintype "passive"))
      (node (ref "T46") (pin "1") (pintype "passive"))
    )
    (net (code "68") (name "Net-(J5-Pad15)") (class "Default")
      (node (ref "J5") (pin "15") (pinfunction "15_15") (pintype "passive"))
      (node (ref "T47") (pin "1") (pintype "passive"))
    )
    (net (code "69") (name "Net-(J5-Pad16)") (class "Default")
      (node (ref "J5") (pin "16") (pinfunction "16_16") (pintype "passive"))
      (node (ref "T51") (pin "1") (pintype "passive"))
    )
    (net (code "70") (name "Net-(J5-Pad17)") (class "Default")
      (node (ref "J5") (pin "17") (pinfunction "17_17") (pintype "passive"))
      (node (ref "T52") (pin "1") (pintype "passive"))
    )
    (net (code "71") (name "Net-(J5-Pad18)") (class "Default")
      (node (ref "J5") (pin "18") (pinfunction "18_18") (pintype "passive"))
      (node (ref "T56") (pin "1") (pintype "passive"))
    )
    (net (code "72") (name "Net-(J5-Pad19)") (class "Default")
      (node (ref "J5") (pin "19") (pinfunction "19_19") (pintype "passive"))
      (node (ref "T57") (pin "1") (pintype "passive"))
    )
    (net (code "73") (name "Net-(J5-Pad20)") (class "Default")
      (node (ref "J5") (pin "20") (pinfunction "20_20") (pintype "passive"))
      (node (ref "T62") (pin "1") (pintype "passive"))
    )
    (net (code "74") (name "Net-(J5-Pad21)") (class "Default")
      (node (ref "J5") (pin "21") (pinfunction "21_21") (pintype "passive"))
      (node (ref "T63") (pin "1") (pintype "passive"))
    )
    (net (code "75") (name "Net-(J5-Pad22)") (class "Default")
      (node (ref "J5") (pin "22") (pinfunction "22_22") (pintype "passive"))
      (node (ref "T67") (pin "1") (pintype "passive"))
    )
    (net (code "76") (name "Net-(J5-Pad23)") (class "Default")
      (node (ref "J5") (pin "23") (pinfunction "23_23") (pintype "passive"))
      (node (ref "T68") (pin "1") (pintype "passive"))
    )
    (net (code "77") (name "Net-(J5-Pad24)") (class "Default")
      (node (ref "J5") (pin "24") (pinfunction "24_24") (pintype "passive"))
      (node (ref "T72") (pin "1") (pintype "passive"))
    )
    (net (code "78") (name "Net-(J5-Pad25)") (class "Default")
      (node (ref "J5") (pin "25") (pinfunction "25_25") (pintype "passive"))
      (node (ref "T73") (pin "1") (pintype "passive"))
    )
    (net (code "79") (name "Net-(J5-Pad26)") (class "Default")
      (node (ref "J5") (pin "26") (pinfunction "26_26") (pintype "passive"))
      (node (ref "T77") (pin "1") (pintype "passive"))
    )
    (net (code "80") (name "Net-(J6-Pad5)") (class "Default")
      (node (ref "J6") (pin "5") (pinfunction "5_5") (pintype "passive"))
      (node (ref "T86") (pin "1") (pintype "passive"))
    )
    (net (code "81") (name "Net-(J6-Pad6)") (class "Default")
      (node (ref "J6") (pin "6") (pinfunction "6_6") (pintype "passive"))
      (node (ref "T84") (pin "1") (pintype "passive"))
    )
    (net (code "82") (name "Net-(J6-Pad8)") (class "Default")
      (node (ref "J6") (pin "8") (pinfunction "8_8") (pintype "passive"))
      (node (ref "T82") (pin "1") (pintype "passive"))
    )
    (net (code "83") (name "Net-(J6-Pad9)") (class "Default")
      (node (ref "J6") (pin "9") (pinfunction "9_9") (pintype "passive"))
      (node (ref "T80") (pin "1") (pintype "passive"))
    )
    (net (code "84") (name "Net-(J6-Pad11)") (class "Default")
      (node (ref "J6") (pin "11") (pinfunction "11_11") (pintype "passive"))
      (node (ref "T78") (pin "1") (pintype "passive"))
    )
    (net (code "85") (name "Net-(J6-Pad12)") (class "Default")
      (node (ref "J6") (pin "12") (pinfunction "12_12") (pintype "passive"))
      (node (ref "T74") (pin "1") (pintype "passive"))
    )
    (net (code "86") (name "P3V3D") (class "Default")
      (node (ref "J1") (pin "1") (pinfunction "1_1") (pintype "passive"))
      (node (ref "J1") (pin "2") (pinfunction "2_2") (pintype "passive"))
      (node (ref "J1") (pin "3") (pinfunction "3_3") (pintype "passive"))
      (node (ref "J1") (pin "4") (pinfunction "4_4") (pintype "passive"))
      (node (ref "J1") (pin "5") (pinfunction "5_5") (pintype "passive"))
      (node (ref "J1") (pin "6") (pinfunction "6_6") (pintype "passive"))
      (node (ref "J2") (pin "21") (pinfunction "21_21") (pintype "passive"))
      (node (ref "J2") (pin "22") (pinfunction "22_22") (pintype "passive"))
      (node (ref "J2") (pin "23") (pinfunction "23_23") (pintype "passive"))
      (node (ref "J2") (pin "24") (pinfunction "24_24") (pintype "passive"))
      (node (ref "J2") (pin "25") (pinfunction "25_25") (pintype "passive"))
      (node (ref "J2") (pin "26") (pinfunction "26_26") (pintype "passive"))
      (node (ref "T1") (pin "1") (pintype "passive"))
    )
    (net (code "87") (name "P3V3D_1") (class "Default")
      (node (ref "J3") (pin "21") (pinfunction "21_21") (pintype "passive"))
      (node (ref "J3") (pin "22") (pinfunction "22_22") (pintype "passive"))
      (node (ref "J3") (pin "23") (pinfunction "23_23") (pintype "passive"))
      (node (ref "J3") (pin "24") (pinfunction "24_24") (pintype "passive"))
      (node (ref "J3") (pin "25") (pinfunction "25_25") (pintype "passive"))
      (node (ref "J3") (pin "26") (pinfunction "26_26") (pintype "passive"))
      (node (ref "J4") (pin "22") (pinfunction "22_22") (pintype "passive"))
      (node (ref "T22") (pin "1") (pintype "passive"))
    )
    (net (code "88") (name "P3V3D_2") (class "Default")
      (node (ref "J5") (pin "1") (pinfunction "1_1") (pintype "passive"))
      (node (ref "J5") (pin "2") (pinfunction "2_2") (pintype "passive"))
      (node (ref "J5") (pin "3") (pinfunction "3_3") (pintype "passive"))
      (node (ref "J5") (pin "4") (pinfunction "4_4") (pintype "passive"))
      (node (ref "J5") (pin "5") (pinfunction "5_5") (pintype "passive"))
      (node (ref "J5") (pin "6") (pinfunction "6_6") (pintype "passive"))
      (node (ref "J6") (pin "1") (pinfunction "1_1") (pintype "passive"))
      (node (ref "T20") (pin "1") (pintype "passive"))
    )
    (net (code "89") (name "unconnected-(FID1-FID-Pad1)") (class "Default")
      (node (ref "FID1") (pin "1") (pinfunction "FID_1") (pintype "passive"))
    )
    (net (code "90") (name "unconnected-(FID2-FID-Pad1)") (class "Default")
      (node (ref "FID2") (pin "1") (pinfunction "FID_1") (pintype "passive"))
    )
    (net (code "91") (name "unconnected-(FID3-FID-Pad1)") (class "Default")
      (node (ref "FID3") (pin "1") (pinfunction "FID_1") (pintype "passive"))
    )
    (net (code "92") (name "unconnected-(FID4-FID-Pad1)") (class "Default")
      (node (ref "FID4") (pin "1") (pinfunction "FID_1") (pintype "passive"))
    )
    (net (code "93") (name "unconnected-(FID5-FID-Pad1)") (class "Default")
      (node (ref "FID5") (pin "1") (pinfunction "FID_1") (pintype "passive"))
    )
    (net (code "94") (name "unconnected-(FID6-FID-Pad1)") (class "Default")
      (node (ref "FID6") (pin "1") (pinfunction "FID_1") (pintype "passive"))
    )
  )
)
